# 6_power_dcdc.net
KiCad netlist of a schematic drawn in Altium Designer
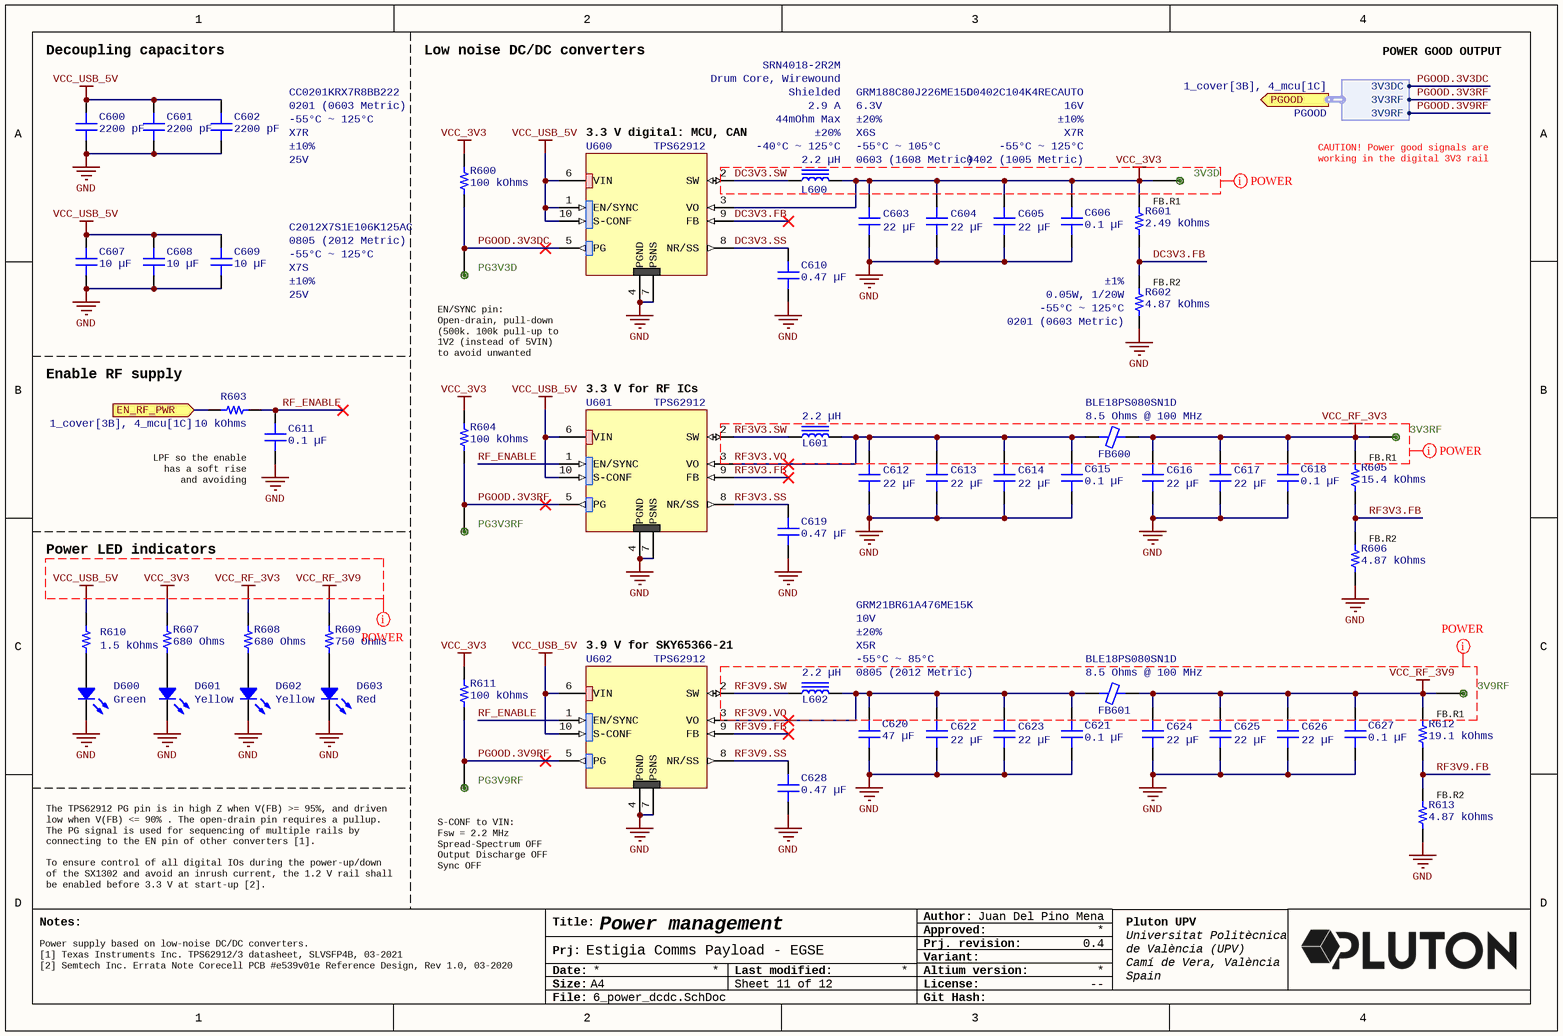
[diagram p0: 6_power_dcdc.SchDoc]

(export (version "E")
  (design (tool "Eeschema 10.0.6"))
  (components
    (comp (ref "3V3D")
      (value "~")
      (footprint "testpoints:testpoint_via")
      (description "Test point, thru-hole")
      (libsource (lib "testpoints") (part "TestPoint-VIA"))
    )
    (comp (ref "3V3RF")
      (value "~")
      (footprint "testpoints:testpoint_via")
      (description "Test point, thru-hole")
      (libsource (lib "testpoints") (part "TestPoint-VIA"))
    )
    (comp (ref "3V9RF")
      (value "~")
      (footprint "testpoints:testpoint_via")
      (description "Test point, thru-hole")
      (libsource (lib "testpoints") (part "TestPoint-VIA"))
    )
    (comp (ref "C600")
      (value "2200 pF")
      (footprint "CAP 0201_0603")
      (description "CAP CER 2200PF 25V X7R 0201")
      (fields (field (name "PART NUMBER") "CC0201KRX7R8BB222") (field (name "MANUFACTURER") "Yageo"))
      (libsource (lib "Celestial Altium Library - altium_library") (part "Capacitor"))
    )
    (comp (ref "C601")
      (value "2200 pF")
      (footprint "CAP 0201_0603")
      (description "CAP CER 2200PF 25V X7R 0201")
      (fields (field (name "PART NUMBER") "CC0201KRX7R8BB222") (field (name "MANUFACTURER") "Yageo"))
      (libsource (lib "Celestial Altium Library - altium_library") (part "Capacitor"))
    )
    (comp (ref "C602")
      (value "2200 pF")
      (footprint "CAP 0201_0603")
      (description "CAP CER 2200PF 25V X7R 0201")
      (fields
        (field (name "PART NUMBER") "CC0201KRX7R8BB222")
        (field (name "DEVICE PACKAGE") "0201 (0603 Metric)")
        (field (name "MANUFACTURER") "Yageo")
        (field (name "OPERATING TEMPERATURE") "-55°C ~ 125°C")
        (field (name "TEMPERATURE COEFFICIENT") "X7R")
        (field (name "TOLERANCE") "±10%")
        (field (name "VOLTAGE - RATED") "25V")
      )
      (libsource (lib "Celestial Altium Library - altium_library") (part "Capacitor"))
    )
    (comp (ref "C603")
      (value "22 µF")
      (footprint "CAP 0603_1608")
      (description "CAP CER 22UF 6.3V X6S 0603")
      (fields
        (field (name "PART NUMBER") "GRM188C80J226ME15D")
        (field (name "DEVICE PACKAGE") "0603 (1608 Metric)")
        (field (name "MANUFACTURER") "Murata Electronics")
        (field (name "OPERATING TEMPERATURE") "-55°C ~ 105°C")
        (field (name "TEMPERATURE COEFFICIENT") "X6S")
        (field (name "TOLERANCE") "±20%")
        (field (name "VOLTAGE - RATED") "6.3V")
      )
      (libsource (lib "Celestial Altium Library - altium_library") (part "Capacitor"))
    )
    (comp (ref "C604")
      (value "22 µF")
      (footprint "CAP 0603_1608")
      (description "CAP CER 22UF 6.3V X6S 0603")
      (fields
        (field (name "PART NUMBER") "GRM188C80J226ME15D")
        (field (name "MANUFACTURER") "Murata Electronics")
      )
      (libsource (lib "Celestial Altium Library - altium_library") (part "Capacitor"))
    )
    (comp (ref "C605")
      (value "22 µF")
      (footprint "CAP 0603_1608")
      (description "CAP CER 22UF 6.3V X6S 0603")
      (fields
        (field (name "PART NUMBER") "GRM188C80J226ME15D")
        (field (name "MANUFACTURER") "Murata Electronics")
      )
      (libsource (lib "Celestial Altium Library - altium_library") (part "Capacitor"))
    )
    (comp (ref "C606")
      (value "0.1 µF")
      (footprint "CAP 0402_1005")
      (description "CAP CER 0402 0.1UF 16V X7R 10%")
      (fields
        (field (name "PART NUMBER") "C0402C104K4RECAUTO")
        (field (name "MANUFACTURER") "KEMET")
        (field (name "OPERATING TEMPERATURE") "-55°C ~ 125°C")
        (field (name "PACKAGE / CASE") "0402 (1005 Metric)")
        (field (name "TEMPERATURE COEFFICIENT") "X7R")
        (field (name "TOLERANCE") "±10%")
        (field (name "VOLTAGE - RATED") "16V")
      )
      (libsource (lib "Celestial Altium Library - altium_library") (part "Capacitor"))
    )
    (comp (ref "C607")
      (value "10 µF")
      (footprint "CAP 0805_2012")
      (description "CAP CER 10UF 25V X7S 0805")
      (fields
        (field (name "PART NUMBER") "C2012X7S1E106K125AC")
        (field (name "MANUFACTURER") "TDK Corporation")
      )
      (libsource (lib "Celestial Altium Library - altium_library") (part "Capacitor"))
    )
    (comp (ref "C608")
      (value "10 µF")
      (footprint "CAP 0805_2012")
      (description "CAP CER 10UF 25V X7S 0805")
      (fields
        (field (name "PART NUMBER") "C2012X7S1E106K125AC")
        (field (name "MANUFACTURER") "TDK Corporation")
      )
      (libsource (lib "Celestial Altium Library - altium_library") (part "Capacitor"))
    )
    (comp (ref "C609")
      (value "10 µF")
      (footprint "CAP 0805_2012")
      (description "CAP CER 10UF 25V X7S 0805")
      (fields
        (field (name "PART NUMBER") "C2012X7S1E106K125AC")
        (field (name "DEVICE PACKAGE") "0805 (2012 Metric)")
        (field (name "MANUFACTURER") "TDK Corporation")
        (field (name "OPERATING TEMPERATURE") "-55°C ~ 125°C")
        (field (name "TEMPERATURE COEFFICIENT") "X7S")
        (field (name "TOLERANCE") "±10%")
        (field (name "VOLTAGE - RATED") "25V")
      )
      (libsource (lib "Celestial Altium Library - altium_library") (part "Capacitor"))
    )
    (comp (ref "C610")
      (value "0.47 µF")
      (footprint "CAP 0402_1005")
      (description "CAP CER 0.47UF 16V X7S 0402")
      (fields
        (field (name "PART NUMBER") "CGA2B1X7S1C474K050BC")
        (field (name "MANUFACTURER") "TDK Corporation")
      )
      (libsource (lib "Celestial Altium Library - altium_library") (part "Capacitor"))
    )
    (comp (ref "C611")
      (value "0.1 µF")
      (footprint "CAP 0402_1005")
      (description "CAP CER 0402 0.1UF 16V X7R 10%")
      (fields (field (name "PART NUMBER") "C0402C104K4RECAUTO") (field (name "MANUFACTURER") "KEMET"))
      (libsource (lib "Celestial Altium Library - altium_library") (part "Capacitor"))
    )
    (comp (ref "C612")
      (value "22 µF")
      (footprint "CAP 0603_1608")
      (description "CAP CER 22UF 6.3V X6S 0603")
      (fields
        (field (name "PART NUMBER") "GRM188C80J226ME15D")
        (field (name "MANUFACTURER") "Murata Electronics")
      )
      (libsource (lib "Celestial Altium Library - altium_library") (part "Capacitor"))
    )
    (comp (ref "C613")
      (value "22 µF")
      (footprint "CAP 0603_1608")
      (description "CAP CER 22UF 6.3V X6S 0603")
      (fields
        (field (name "PART NUMBER") "GRM188C80J226ME15D")
        (field (name "MANUFACTURER") "Murata Electronics")
      )
      (libsource (lib "Celestial Altium Library - altium_library") (part "Capacitor"))
    )
    (comp (ref "C614")
      (value "22 µF")
      (footprint "CAP 0603_1608")
      (description "CAP CER 22UF 6.3V X6S 0603")
      (fields
        (field (name "PART NUMBER") "GRM188C80J226ME15D")
        (field (name "MANUFACTURER") "Murata Electronics")
      )
      (libsource (lib "Celestial Altium Library - altium_library") (part "Capacitor"))
    )
    (comp (ref "C615")
      (value "0.1 µF")
      (footprint "CAP 0402_1005")
      (description "CAP CER 0402 0.1UF 16V X7R 10%")
      (fields (field (name "PART NUMBER") "C0402C104K4RECAUTO") (field (name "MANUFACTURER") "KEMET"))
      (libsource (lib "Celestial Altium Library - altium_library") (part "Capacitor"))
    )
    (comp (ref "C616")
      (value "22 µF")
      (footprint "CAP 0603_1608")
      (description "CAP CER 22UF 6.3V X6S 0603")
      (fields
        (field (name "PART NUMBER") "GRM188C80J226ME15D")
        (field (name "MANUFACTURER") "Murata Electronics")
      )
      (libsource (lib "Celestial Altium Library - altium_library") (part "Capacitor"))
    )
    (comp (ref "C617")
      (value "22 µF")
      (footprint "CAP 0603_1608")
      (description "CAP CER 22UF 6.3V X6S 0603")
      (fields
        (field (name "PART NUMBER") "GRM188C80J226ME15D")
        (field (name "MANUFACTURER") "Murata Electronics")
      )
      (libsource (lib "Celestial Altium Library - altium_library") (part "Capacitor"))
    )
    (comp (ref "C618")
      (value "0.1 µF")
      (footprint "CAP 0402_1005")
      (description "CAP CER 0402 0.1UF 16V X7R 10%")
      (fields (field (name "PART NUMBER") "C0402C104K4RECAUTO") (field (name "MANUFACTURER") "KEMET"))
      (libsource (lib "Celestial Altium Library - altium_library") (part "Capacitor"))
    )
    (comp (ref "C619")
      (value "0.47 µF")
      (footprint "CAP 0402_1005")
      (description "CAP CER 0.47UF 16V X7S 0402")
      (fields
        (field (name "PART NUMBER") "CGA2B1X7S1C474K050BC")
        (field (name "MANUFACTURER") "TDK Corporation")
      )
      (libsource (lib "Celestial Altium Library - altium_library") (part "Capacitor"))
    )
    (comp (ref "C620")
      (value "47 µF")
      (footprint "CAP 0805_2012")
      (description "CAP CER 47UF 10V X5R 0805")
      (fields
        (field (name "PART NUMBER") "GRM21BR61A476ME15K")
        (field (name "DEVICE PACKAGE") "0805 (2012 Metric)")
        (field (name "MANUFACTURER") "Murata Electronics")
        (field (name "OPERATING TEMPERATURE") "-55°C ~ 85°C")
        (field (name "TEMPERATURE COEFFICIENT") "X5R")
        (field (name "TOLERANCE") "±20%")
        (field (name "VOLTAGE - RATED") "10V")
      )
      (libsource (lib "Celestial Altium Library - altium_library") (part "Capacitor"))
    )
    (comp (ref "C621")
      (value "0.1 µF")
      (footprint "CAP 0402_1005")
      (description "CAP CER 0402 0.1UF 16V X7R 10%")
      (fields (field (name "PART NUMBER") "C0402C104K4RECAUTO") (field (name "MANUFACTURER") "KEMET"))
      (libsource (lib "Celestial Altium Library - altium_library") (part "Capacitor"))
    )
    (comp (ref "C622")
      (value "22 µF")
      (footprint "CAP 0603_1608")
      (description "CAP CER 22UF 6.3V X6S 0603")
      (fields
        (field (name "PART NUMBER") "GRM188C80J226ME15D")
        (field (name "MANUFACTURER") "Murata Electronics")
      )
      (libsource (lib "Celestial Altium Library - altium_library") (part "Capacitor"))
    )
    (comp (ref "C623")
      (value "22 µF")
      (footprint "CAP 0603_1608")
      (description "CAP CER 22UF 6.3V X6S 0603")
      (fields
        (field (name "PART NUMBER") "GRM188C80J226ME15D")
        (field (name "MANUFACTURER") "Murata Electronics")
      )
      (libsource (lib "Celestial Altium Library - altium_library") (part "Capacitor"))
    )
    (comp (ref "C624")
      (value "22 µF")
      (footprint "CAP 0603_1608")
      (description "CAP CER 22UF 6.3V X6S 0603")
      (fields
        (field (name "PART NUMBER") "GRM188C80J226ME15D")
        (field (name "MANUFACTURER") "Murata Electronics")
      )
      (libsource (lib "Celestial Altium Library - altium_library") (part "Capacitor"))
    )
    (comp (ref "C625")
      (value "22 µF")
      (footprint "CAP 0603_1608")
      (description "CAP CER 22UF 6.3V X6S 0603")
      (fields
        (field (name "PART NUMBER") "GRM188C80J226ME15D")
        (field (name "MANUFACTURER") "Murata Electronics")
      )
      (libsource (lib "Celestial Altium Library - altium_library") (part "Capacitor"))
    )
    (comp (ref "C626")
      (value "22 µF")
      (footprint "CAP 0603_1608")
      (description "CAP CER 22UF 6.3V X6S 0603")
      (fields
        (field (name "PART NUMBER") "GRM188C80J226ME15D")
        (field (name "MANUFACTURER") "Murata Electronics")
      )
      (libsource (lib "Celestial Altium Library - altium_library") (part "Capacitor"))
    )
    (comp (ref "C627")
      (value "0.1 µF")
      (footprint "CAP 0402_1005")
      (description "CAP CER 0402 0.1UF 16V X7R 10%")
      (fields (field (name "PART NUMBER") "C0402C104K4RECAUTO") (field (name "MANUFACTURER") "KEMET"))
      (libsource (lib "Celestial Altium Library - altium_library") (part "Capacitor"))
    )
    (comp (ref "C628")
      (value "0.47 µF")
      (footprint "CAP 0402_1005")
      (description "CAP CER 0.47UF 16V X7S 0402")
      (fields
        (field (name "PART NUMBER") "CGA2B1X7S1C474K050BC")
        (field (name "MANUFACTURER") "TDK Corporation")
      )
      (libsource (lib "Celestial Altium Library - altium_library") (part "Capacitor"))
    )
    (comp (ref "D600")
      (value "Green")
      (footprint "LED 0402_1005 GREEN")
      (description "LED GREEN CLEAR 2SMD")
      (fields
        (field (name "PART NUMBER") "EAST10052GA0")
        (field (name "COLOR") "Green")
        (field (name "MANUFACTURER") "Everlight Electronics Co Ltd")
      )
      (libsource (lib "Celestial Altium Library - altium_library") (part "LED"))
    )
    (comp (ref "D601")
      (value "Yellow")
      (footprint "LED 0402_1005 YELLOW")
      (description "LED YELLOW CLEAR 1005 SMD")
      (fields
        (field (name "PART NUMBER") "FHY1105P-TR")
        (field (name "COLOR") "Yellow")
        (field (name "MANUFACTURER") "Stanley Electric Co")
      )
      (libsource (lib "Celestial Altium Library - altium_library") (part "LED"))
    )
    (comp (ref "D602")
      (value "Yellow")
      (footprint "LED 0402_1005 YELLOW")
      (description "LED YELLOW CLEAR 1005 SMD")
      (fields
        (field (name "PART NUMBER") "FHY1105P-TR")
        (field (name "COLOR") "Yellow")
        (field (name "MANUFACTURER") "Stanley Electric Co")
      )
      (libsource (lib "Celestial Altium Library - altium_library") (part "LED"))
    )
    (comp (ref "D603")
      (value "Red")
      (footprint "LED 0402_1005 RED")
      (description "LED RED CLEAR 2SMD")
      (fields
        (field (name "PART NUMBER") "EAST10053RA0")
        (field (name "COLOR") "Red")
        (field (name "MANUFACTURER") "Everlight Electronics Co Ltd")
      )
      (libsource (lib "Celestial Altium Library - altium_library") (part "LED"))
    )
    (comp (ref "FB600")
      (value "8.5 Ohms @ 100 MHz")
      (footprint "FER 0603_1608")
      (description "FERRITE BEAD 8.5 OHM 0603 1LN")
      (fields
        (field (name "PART NUMBER") "BLE18PS080SN1D")
        (field (name "IMPEDANCE @ FREQUENCY") "8.5 Ohms @ 100 MHz")
        (field (name "MANUFACTURER") "Murata Electronics")
      )
      (libsource (lib "Celestial Altium Library - altium_library") (part "Ferrite Chip"))
    )
    (comp (ref "FB601")
      (value "8.5 Ohms @ 100 MHz")
      (footprint "FER 0603_1608")
      (description "FERRITE BEAD 8.5 OHM 0603 1LN")
      (fields
        (field (name "PART NUMBER") "BLE18PS080SN1D")
        (field (name "IMPEDANCE @ FREQUENCY") "8.5 Ohms @ 100 MHz")
        (field (name "MANUFACTURER") "Murata Electronics")
      )
      (libsource (lib "Celestial Altium Library - altium_library") (part "Ferrite Chip"))
    )
    (comp (ref "L600")
      (value "2.2 µH")
      (footprint "BOURNS SRN4018")
      (description "FIXED IND 2.2UH 2.9A 44 MOHM SMD")
      (fields
        (field (name "PART NUMBER") "SRN4018-2R2M")
        (field (name "CURRENT RATING (AMPS)") "2.9 A")
        (field (name "DC RESISTANCE (DCR)") "44mOhm Max")
        (field (name "MANUFACTURER") "Bourns Inc.")
        (field (name "OPERATING TEMPERATURE") "-40°C ~ 125°C")
        (field (name "SHIELDING") "Shielded")
        (field (name "TOLERANCE") "±20%")
        (field (name "TYPE") "Drum Core, Wirewound")
      )
      (libsource (lib "Celestial Altium Library - altium_library") (part "Inductor"))
    )
    (comp (ref "L601")
      (value "2.2 µH")
      (footprint "BOURNS SRN4018")
      (description "FIXED IND 2.2UH 2.9A 44 MOHM SMD")
      (fields (field (name "PART NUMBER") "SRN4018-2R2M") (field (name "MANUFACTURER") "Bourns Inc."))
      (libsource (lib "Celestial Altium Library - altium_library") (part "Inductor"))
    )
    (comp (ref "L602")
      (value "2.2 µH")
      (footprint "BOURNS SRN4018")
      (description "FIXED IND 2.2UH 2.9A 44 MOHM SMD")
      (fields (field (name "PART NUMBER") "SRN4018-2R2M") (field (name "MANUFACTURER") "Bourns Inc."))
      (libsource (lib "Celestial Altium Library - altium_library") (part "Inductor"))
    )
    (comp (ref "PG3V3D")
      (value "~")
      (footprint "testpoints:testpoint_via")
      (description "Test point, thru-hole")
      (libsource (lib "testpoints") (part "TestPoint-VIA"))
    )
    (comp (ref "PG3V3RF")
      (value "~")
      (footprint "testpoints:testpoint_via")
      (description "Test point, thru-hole")
      (libsource (lib "testpoints") (part "TestPoint-VIA"))
    )
    (comp (ref "PG3V9RF")
      (value "~")
      (footprint "testpoints:testpoint_via")
      (description "Test point, thru-hole")
      (libsource (lib "testpoints") (part "TestPoint-VIA"))
    )
    (comp (ref "R600")
      (value "100 kOhms")
      (footprint "RES 0201_0603")
      (description "RES 100K OHM 1% 1/20W 0201")
      (fields (field (name "PART NUMBER") "RC0201FR-13100KL") (field (name "MANUFACTURER") "Yageo"))
      (libsource (lib "Celestial Altium Library - altium_library") (part "Resistor"))
    )
    (comp (ref "R601")
      (value "2.49 kOhms")
      (footprint "RES 0201_0603")
      (description "RES SMD 2.49K OHM 1% 1/20W 0201")
      (fields (field (name "PART NUMBER") "AC0201FR-072K49L") (field (name "MANUFACTURER") "Yageo"))
      (libsource (lib "Celestial Altium Library - altium_library") (part "Resistor"))
    )
    (comp (ref "R602")
      (value "4.87 kOhms")
      (footprint "RES 0201_0603")
      (description "RES 4.87K OHM 1% 1/20W 0201")
      (fields
        (field (name "PART NUMBER") "RC0201FR-074K87L")
        (field (name "DEVICE PACKAGE") "0201 (0603 Metric)")
        (field (name "MANUFACTURER") "Yageo")
        (field (name "OPERATING TEMPERATURE") "-55°C ~ 125°C")
        (field (name "POWER (WATTS)") "0.05W, 1/20W")
        (field (name "TOLERANCE") "±1%")
      )
      (libsource (lib "Celestial Altium Library - altium_library") (part "Resistor"))
    )
    (comp (ref "R603")
      (value "10 kOhms")
      (footprint "RES 0201_0603")
      (description "RES SMD 10K OHM 1% 1/20W 0201")
      (fields (field (name "PART NUMBER") "AF0201FR-0710KL") (field (name "MANUFACTURER") "Yageo"))
      (libsource (lib "Celestial Altium Library - altium_library") (part "Resistor"))
    )
    (comp (ref "R604")
      (value "100 kOhms")
      (footprint "RES 0201_0603")
      (description "RES 100K OHM 1% 1/20W 0201")
      (fields (field (name "PART NUMBER") "RC0201FR-13100KL") (field (name "MANUFACTURER") "Yageo"))
      (libsource (lib "Celestial Altium Library - altium_library") (part "Resistor"))
    )
    (comp (ref "R605")
      (value "15.4 kOhms")
      (footprint "RES 0201_0603")
      (description "RES 15.4K OHM 1% 1/20W 0201")
      (fields (field (name "PART NUMBER") "RC0201FR-0715K4L") (field (name "MANUFACTURER") "Yageo"))
      (libsource (lib "Celestial Altium Library - altium_library") (part "Resistor"))
    )
    (comp (ref "R606")
      (value "4.87 kOhms")
      (footprint "RES 0201_0603")
      (description "RES 4.87K OHM 1% 1/20W 0201")
      (fields (field (name "PART NUMBER") "RC0201FR-074K87L") (field (name "MANUFACTURER") "Yageo"))
      (libsource (lib "Celestial Altium Library - altium_library") (part "Resistor"))
    )
    (comp (ref "R607")
      (value "680 Ohms")
      (footprint "RES 0201_0603")
      (description "RES 680 OHM 5% 1/20W 0201")
      (fields (field (name "PART NUMBER") "RC0201JR-07680RL") (field (name "MANUFACTURER") "Yageo"))
      (libsource (lib "Celestial Altium Library - altium_library") (part "Resistor"))
    )
    (comp (ref "R608")
      (value "680 Ohms")
      (footprint "RES 0201_0603")
      (description "RES 680 OHM 5% 1/20W 0201")
      (fields (field (name "PART NUMBER") "RC0201JR-07680RL") (field (name "MANUFACTURER") "Yageo"))
      (libsource (lib "Celestial Altium Library - altium_library") (part "Resistor"))
    )
    (comp (ref "R609")
      (value "750 Ohms")
      (footprint "RES 0201_0603")
      (description "RES 750 OHM 5% 1/20W 0201")
      (fields (field (name "PART NUMBER") "RC0201JR-07750RL") (field (name "MANUFACTURER") "Yageo"))
      (libsource (lib "Celestial Altium Library - altium_library") (part "Resistor"))
    )
    (comp (ref "R610")
      (value "1.5 kOhms")
      (footprint "RES 0201_0603")
      (description "RES SMD 1.5K OHM 5% 1/20W 0201")
      (fields (field (name "PART NUMBER") "CRCW02011K50JNED") (field (name "MANUFACTURER") "Vishay Dale"))
      (libsource (lib "Celestial Altium Library - altium_library") (part "Resistor"))
    )
    (comp (ref "R611")
      (value "100 kOhms")
      (footprint "RES 0201_0603")
      (description "RES 100K OHM 1% 1/20W 0201")
      (fields (field (name "PART NUMBER") "RC0201FR-13100KL") (field (name "MANUFACTURER") "Yageo"))
      (libsource (lib "Celestial Altium Library - altium_library") (part "Resistor"))
    )
    (comp (ref "R612")
      (value "19.1 kOhms")
      (footprint "RES 0201_0603")
      (description "RES 19.1K OHM 1% 1/20W 0201")
      (fields (field (name "PART NUMBER") "RC0201FR-0719K1L") (field (name "MANUFACTURER") "Yageo"))
      (libsource (lib "Celestial Altium Library - altium_library") (part "Resistor"))
    )
    (comp (ref "R613")
      (value "4.87 kOhms")
      (footprint "RES 0201_0603")
      (description "RES 4.87K OHM 1% 1/20W 0201")
      (fields (field (name "PART NUMBER") "RC0201FR-074K87L") (field (name "MANUFACTURER") "Yageo"))
      (libsource (lib "Celestial Altium Library - altium_library") (part "Resistor"))
    )
    (comp (ref "U600")
      (value "TPS62912")
      (footprint "ics:VQFN-HR-TPS6291X")
      (libsource (lib "power") (part "TPS62912"))
    )
    (comp (ref "U601")
      (value "TPS62912")
      (footprint "ics:VQFN-HR-TPS6291X")
      (libsource (lib "power") (part "TPS62912"))
    )
    (comp (ref "U602")
      (value "TPS62912")
      (footprint "ics:VQFN-HR-TPS6291X")
      (libsource (lib "power") (part "TPS62912"))
    )
  )
  (nets
    (net (code "2") (name "/DC3V3.FB") (class "Default")
      (node (ref "R601") (pin "1") (pinfunction "1_1") (pintype "passive"))
      (node (ref "R602") (pin "2") (pinfunction "2_2") (pintype "passive"))
      (node (ref "U600") (pin "9") (pinfunction "FB_9") (pintype "input"))
    )
    (net (code "3") (name "/DC3V3.SS") (class "Default")
      (node (ref "C610") (pin "2") (pinfunction "2_2") (pintype "passive"))
      (node (ref "U600") (pin "8") (pinfunction "NR/SS_8") (pintype "output"))
    )
    (net (code "4") (name "/DC3V3.SW") (class "Default")
      (node (ref "L600") (pin "1") (pinfunction "1_1") (pintype "passive"))
      (node (ref "U600") (pin "2") (pinfunction "SW_2") (pintype "bidirectional"))
    )
    (net (code "5") (name "/EN_RF_PWR") (class "Default")
      (node (ref "R603") (pin "2") (pinfunction "2_2") (pintype "passive"))
    )
    (net (code "6") (name "/PGOOD.3V3DC") (class "Default")
      (node (ref "PG3V3D") (pin "0") (pinfunction "0_0") (pintype "passive"))
      (node (ref "R600") (pin "1") (pinfunction "1_1") (pintype "passive"))
      (node (ref "U600") (pin "5") (pinfunction "PG_5") (pintype "output"))
    )
    (net (code "7") (name "/PGOOD.3V3RF") (class "Default")
      (node (ref "PG3V3RF") (pin "0") (pinfunction "0_0") (pintype "passive"))
      (node (ref "R604") (pin "1") (pinfunction "1_1") (pintype "passive"))
      (node (ref "U601") (pin "5") (pinfunction "PG_5") (pintype "output"))
    )
    (net (code "8") (name "/PGOOD.3V9RF") (class "Default")
      (node (ref "PG3V9RF") (pin "0") (pinfunction "0_0") (pintype "passive"))
      (node (ref "R611") (pin "1") (pinfunction "1_1") (pintype "passive"))
      (node (ref "U602") (pin "5") (pinfunction "PG_5") (pintype "output"))
    )
    (net (code "9") (name "/RF3V3.FB") (class "Default")
      (node (ref "R605") (pin "1") (pinfunction "1_1") (pintype "passive"))
      (node (ref "R606") (pin "2") (pinfunction "2_2") (pintype "passive"))
      (node (ref "U601") (pin "9") (pinfunction "FB_9") (pintype "input"))
    )
    (net (code "10") (name "/RF3V3.SS") (class "Default")
      (node (ref "C619") (pin "2") (pinfunction "2_2") (pintype "passive"))
      (node (ref "U601") (pin "8") (pinfunction "NR/SS_8") (pintype "output"))
    )
    (net (code "11") (name "/RF3V3.SW") (class "Default")
      (node (ref "L601") (pin "1") (pinfunction "1_1") (pintype "passive"))
      (node (ref "U601") (pin "2") (pinfunction "SW_2") (pintype "bidirectional"))
    )
    (net (code "13") (name "/RF3V3.VO") (class "Default")
      (node (ref "C612") (pin "2") (pinfunction "2_2") (pintype "passive"))
      (node (ref "C613") (pin "2") (pinfunction "2_2") (pintype "passive"))
      (node (ref "C614") (pin "2") (pinfunction "2_2") (pintype "passive"))
      (node (ref "C615") (pin "2") (pinfunction "2_2") (pintype "passive"))
      (node (ref "FB600") (pin "1") (pinfunction "1_1") (pintype "passive"))
      (node (ref "L601") (pin "2") (pinfunction "2_2") (pintype "passive"))
      (node (ref "U601") (pin "3") (pinfunction "VO_3") (pintype "input"))
    )
    (net (code "14") (name "/RF3V9.FB") (class "Default")
      (node (ref "R612") (pin "1") (pinfunction "1_1") (pintype "passive"))
      (node (ref "R613") (pin "2") (pinfunction "2_2") (pintype "passive"))
      (node (ref "U602") (pin "9") (pinfunction "FB_9") (pintype "input"))
    )
    (net (code "15") (name "/RF3V9.SS") (class "Default")
      (node (ref "C628") (pin "2") (pinfunction "2_2") (pintype "passive"))
      (node (ref "U602") (pin "8") (pinfunction "NR/SS_8") (pintype "output"))
    )
    (net (code "17") (name "/RF3V9.SW") (class "Default")
      (node (ref "L602") (pin "1") (pinfunction "1_1") (pintype "passive"))
      (node (ref "U602") (pin "2") (pinfunction "SW_2") (pintype "bidirectional"))
    )
    (net (code "19") (name "/RF3V9.VO") (class "Default")
      (node (ref "C620") (pin "2") (pinfunction "2_2") (pintype "passive"))
      (node (ref "C621") (pin "2") (pinfunction "2_2") (pintype "passive"))
      (node (ref "C622") (pin "2") (pinfunction "2_2") (pintype "passive"))
      (node (ref "C623") (pin "2") (pinfunction "2_2") (pintype "passive"))
      (node (ref "FB601") (pin "1") (pinfunction "1_1") (pintype "passive"))
      (node (ref "L602") (pin "2") (pinfunction "2_2") (pintype "passive"))
      (node (ref "U602") (pin "3") (pinfunction "VO_3") (pintype "input"))
    )
    (net (code "20") (name "/RF_ENABLE") (class "Default")
      (node (ref "C611") (pin "2") (pinfunction "2_2") (pintype "passive"))
      (node (ref "R603") (pin "1") (pinfunction "1_1") (pintype "passive"))
      (node (ref "U601") (pin "1") (pinfunction "EN/SYNC_1") (pintype "input"))
      (node (ref "U602") (pin "1") (pinfunction "EN/SYNC_1") (pintype "input"))
    )
    (net (code "21") (name "GND") (class "Default")
      (node (ref "C600") (pin "1") (pinfunction "1_1") (pintype "passive"))
      (node (ref "C601") (pin "1") (pinfunction "1_1") (pintype "passive"))
      (node (ref "C602") (pin "1") (pinfunction "1_1") (pintype "passive"))
      (node (ref "C603") (pin "1") (pinfunction "1_1") (pintype "passive"))
      (node (ref "C604") (pin "1") (pinfunction "1_1") (pintype "passive"))
      (node (ref "C605") (pin "1") (pinfunction "1_1") (pintype "passive"))
      (node (ref "C606") (pin "1") (pinfunction "1_1") (pintype "passive"))
      (node (ref "C607") (pin "1") (pinfunction "1_1") (pintype "passive"))
      (node (ref "C608") (pin "1") (pinfunction "1_1") (pintype "passive"))
      (node (ref "C609") (pin "1") (pinfunction "1_1") (pintype "passive"))
      (node (ref "C610") (pin "1") (pinfunction "1_1") (pintype "passive"))
      (node (ref "C611") (pin "1") (pinfunction "1_1") (pintype "passive"))
      (node (ref "C612") (pin "1") (pinfunction "1_1") (pintype "passive"))
      (node (ref "C613") (pin "1") (pinfunction "1_1") (pintype "passive"))
      (node (ref "C614") (pin "1") (pinfunction "1_1") (pintype "passive"))
      (node (ref "C615") (pin "1") (pinfunction "1_1") (pintype "passive"))
      (node (ref "C616") (pin "1") (pinfunction "1_1") (pintype "passive"))
      (node (ref "C617") (pin "1") (pinfunction "1_1") (pintype "passive"))
      (node (ref "C618") (pin "1") (pinfunction "1_1") (pintype "passive"))
      (node (ref "C619") (pin "1") (pinfunction "1_1") (pintype "passive"))
      (node (ref "C620") (pin "1") (pinfunction "1_1") (pintype "passive"))
      (node (ref "C621") (pin "1") (pinfunction "1_1") (pintype "passive"))
      (node (ref "C622") (pin "1") (pinfunction "1_1") (pintype "passive"))
      (node (ref "C623") (pin "1") (pinfunction "1_1") (pintype "passive"))
      (node (ref "C624") (pin "1") (pinfunction "1_1") (pintype "passive"))
      (node (ref "C625") (pin "1") (pinfunction "1_1") (pintype "passive"))
      (node (ref "C626") (pin "1") (pinfunction "1_1") (pintype "passive"))
      (node (ref "C627") (pin "1") (pinfunction "1_1") (pintype "passive"))
      (node (ref "C628") (pin "1") (pinfunction "1_1") (pintype "passive"))
      (node (ref "D600") (pin "2") (pinfunction "2_2") (pintype "passive"))
      (node (ref "D601") (pin "2") (pinfunction "2_2") (pintype "passive"))
      (node (ref "D602") (pin "2") (pinfunction "2_2") (pintype "passive"))
      (node (ref "D603") (pin "2") (pinfunction "2_2") (pintype "passive"))
      (node (ref "R602") (pin "1") (pinfunction "1_1") (pintype "passive"))
      (node (ref "R606") (pin "1") (pinfunction "1_1") (pintype "passive"))
      (node (ref "R613") (pin "1") (pinfunction "1_1") (pintype "passive"))
      (node (ref "U600") (pin "4") (pinfunction "PGND_4") (pintype "passive"))
      (node (ref "U600") (pin "7") (pinfunction "PSNS_7") (pintype "power_in"))
      (node (ref "U601") (pin "4") (pinfunction "PGND_4") (pintype "passive"))
      (node (ref "U601") (pin "7") (pinfunction "PSNS_7") (pintype "power_in"))
      (node (ref "U602") (pin "4") (pinfunction "PGND_4") (pintype "passive"))
      (node (ref "U602") (pin "7") (pinfunction "PSNS_7") (pintype "power_in"))
    )
    (net (code "22") (name "Net-(D600-Pad1)") (class "Default")
      (node (ref "D600") (pin "1") (pinfunction "1_1") (pintype "passive"))
      (node (ref "R610") (pin "1") (pinfunction "1_1") (pintype "passive"))
    )
    (net (code "23") (name "Net-(D601-Pad1)") (class "Default")
      (node (ref "D601") (pin "1") (pinfunction "1_1") (pintype "passive"))
      (node (ref "R607") (pin "1") (pinfunction "1_1") (pintype "passive"))
    )
    (net (code "24") (name "Net-(D602-Pad1)") (class "Default")
      (node (ref "D602") (pin "1") (pinfunction "1_1") (pintype "passive"))
      (node (ref "R608") (pin "1") (pinfunction "1_1") (pintype "passive"))
    )
    (net (code "25") (name "Net-(D603-Pad1)") (class "Default")
      (node (ref "D603") (pin "1") (pinfunction "1_1") (pintype "passive"))
      (node (ref "R609") (pin "1") (pinfunction "1_1") (pintype "passive"))
    )
    (net (code "26") (name "VCC_3V3") (class "Default")
      (node (ref "3V3D") (pin "0") (pinfunction "0_0") (pintype "passive"))
      (node (ref "C603") (pin "2") (pinfunction "2_2") (pintype "passive"))
      (node (ref "C604") (pin "2") (pinfunction "2_2") (pintype "passive"))
      (node (ref "C605") (pin "2") (pinfunction "2_2") (pintype "passive"))
      (node (ref "C606") (pin "2") (pinfunction "2_2") (pintype "passive"))
      (node (ref "L600") (pin "2") (pinfunction "2_2") (pintype "passive"))
      (node (ref "R600") (pin "2") (pinfunction "2_2") (pintype "passive"))
      (node (ref "R601") (pin "2") (pinfunction "2_2") (pintype "passive"))
      (node (ref "R604") (pin "2") (pinfunction "2_2") (pintype "passive"))
      (node (ref "R607") (pin "2") (pinfunction "2_2") (pintype "passive"))
      (node (ref "R611") (pin "2") (pinfunction "2_2") (pintype "passive"))
      (node (ref "U600") (pin "3") (pinfunction "VO_3") (pintype "input"))
    )
    (net (code "27") (name "VCC_RF_3V3") (class "Default")
      (node (ref "3V3RF") (pin "0") (pinfunction "0_0") (pintype "passive"))
      (node (ref "C616") (pin "2") (pinfunction "2_2") (pintype "passive"))
      (node (ref "C617") (pin "2") (pinfunction "2_2") (pintype "passive"))
      (node (ref "C618") (pin "2") (pinfunction "2_2") (pintype "passive"))
      (node (ref "FB600") (pin "2") (pinfunction "2_2") (pintype "passive"))
      (node (ref "R605") (pin "2") (pinfunction "2_2") (pintype "passive"))
      (node (ref "R608") (pin "2") (pinfunction "2_2") (pintype "passive"))
    )
    (net (code "28") (name "VCC_RF_3V9") (class "Default")
      (node (ref "3V9RF") (pin "0") (pinfunction "0_0") (pintype "passive"))
      (node (ref "C624") (pin "2") (pinfunction "2_2") (pintype "passive"))
      (node (ref "C625") (pin "2") (pinfunction "2_2") (pintype "passive"))
      (node (ref "C626") (pin "2") (pinfunction "2_2") (pintype "passive"))
      (node (ref "C627") (pin "2") (pinfunction "2_2") (pintype "passive"))
      (node (ref "FB601") (pin "2") (pinfunction "2_2") (pintype "passive"))
      (node (ref "R609") (pin "2") (pinfunction "2_2") (pintype "passive"))
      (node (ref "R612") (pin "2") (pinfunction "2_2") (pintype "passive"))
    )
    (net (code "29") (name "VCC_USB_5V") (class "Default")
      (node (ref "C600") (pin "2") (pinfunction "2_2") (pintype "passive"))
      (node (ref "C601") (pin "2") (pinfunction "2_2") (pintype "passive"))
      (node (ref "C602") (pin "2") (pinfunction "2_2") (pintype "passive"))
      (node (ref "C607") (pin "2") (pinfunction "2_2") (pintype "passive"))
      (node (ref "C608") (pin "2") (pinfunction "2_2") (pintype "passive"))
      (node (ref "C609") (pin "2") (pinfunction "2_2") (pintype "passive"))
      (node (ref "R610") (pin "2") (pinfunction "2_2") (pintype "passive"))
      (node (ref "U600") (pin "1") (pinfunction "EN/SYNC_1") (pintype "input"))
      (node (ref "U600") (pin "10") (pinfunction "S-CONF_10") (pintype "input"))
      (node (ref "U600") (pin "6") (pinfunction "VIN_6") (pintype "power_in"))
      (node (ref "U601") (pin "10") (pinfunction "S-CONF_10") (pintype "input"))
      (node (ref "U601") (pin "6") (pinfunction "VIN_6") (pintype "power_in"))
      (node (ref "U602") (pin "10") (pinfunction "S-CONF_10") (pintype "input"))
      (node (ref "U602") (pin "6") (pinfunction "VIN_6") (pintype "power_in"))
    )
  )
)
